# Voeding.net
KiCad netlist of a schematic drawn in Altium Designer
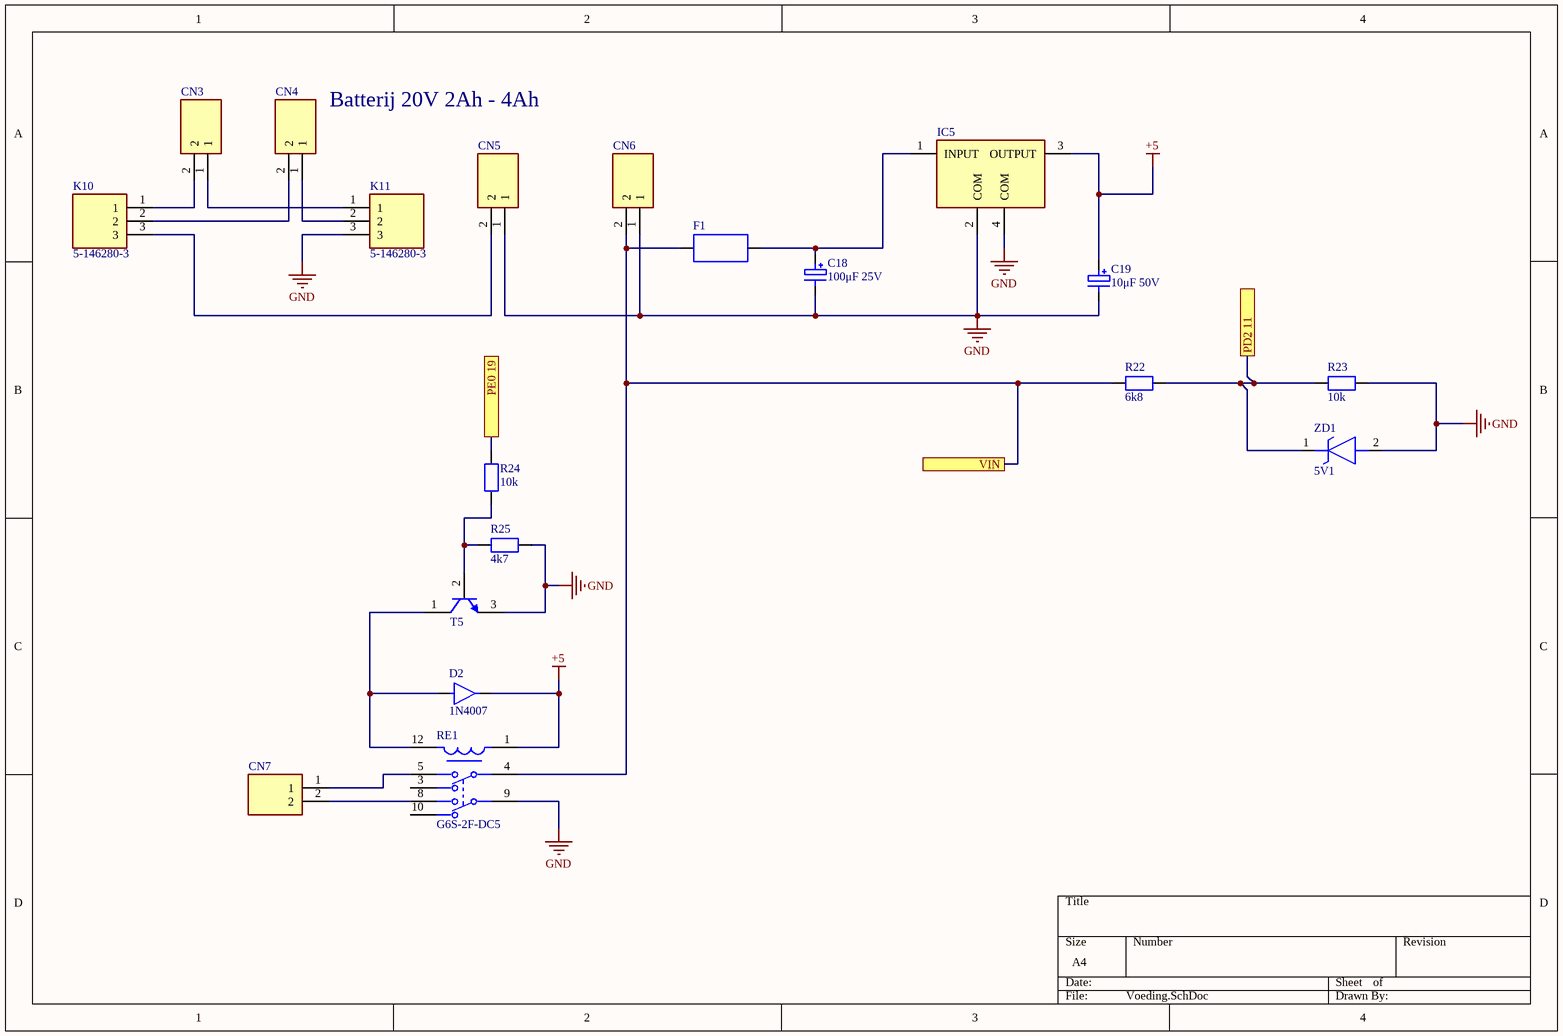
[diagram p0: Voeding.SchDoc]

(export (version "E")
  (design (tool "Eeschema 10.0.6"))
  (components
    (comp (ref "C18")
      (value "100μF 25V")
      (footprint "Elco 100uF 25V")
      (fields
        (field (name "PART NUMBER") "02015A270JAT2A")
        (field (name "MANUFACTURER") "AVX Interconnect / Elco")
      )
      (libsource (lib "Soldeerstation") (part "Condensator Elco"))
    )
    (comp (ref "C19")
      (value "10μF 50V")
      (footprint "Elco 100uF 25V")
      (fields
        (field (name "PART NUMBER") "02015A270JAT2A")
        (field (name "MANUFACTURER") "AVX Interconnect / Elco")
      )
      (libsource (lib "Soldeerstation") (part "Condensator Elco"))
    )
    (comp (ref "CN3")
      (value "282836-2")
      (footprint "Schroefconnector 2 Pin")
      (description "Connector")
      (libsource (lib "Soldeerstation") (part "Schroefconnector 2 Pin L"))
    )
    (comp (ref "CN4")
      (value "282836-2")
      (footprint "Schroefconnector 2 Pin")
      (description "Connector")
      (libsource (lib "Soldeerstation") (part "Schroefconnector 2 Pin L"))
    )
    (comp (ref "CN5")
      (value "282836-2")
      (footprint "Schroefconnector 2 Pin")
      (description "Connector")
      (libsource (lib "Soldeerstation") (part "Schroefconnector 2 Pin L"))
    )
    (comp (ref "CN6")
      (value "282836-2")
      (footprint "Schroefconnector 2 Pin")
      (description "Connector")
      (libsource (lib "Soldeerstation") (part "Schroefconnector 2 Pin L"))
    )
    (comp (ref "CN7")
      (value "282836-2")
      (footprint "Schroefconnector 2 Pin")
      (description "Connector")
      (libsource (lib "") (part "Schroefconnector 2 Pin L_1"))
    )
    (comp (ref "D2")
      (value "1N4007")
      (footprint "1N4007")
      (description "1000 V, 1 A")
      (fields (field (name "VOLTAGE") "100V"))
      (libsource (lib "Soldeerstation") (part "1N4007"))
    )
    (comp (ref "F1")
      (value "696101000002")
      (footprint "FuseHolder")
      (libsource (lib "Soldeerstation") (part "FuseHolder"))
    )
    (comp (ref "IC5")
      (value "TL780-05CKTTR")
      (footprint "DC-DC Convertor")
      (description "IC REG LIN 5V 1.5A DDPAK/TO263-3")
      (libsource (lib "Soldeerstation") (part "DC/DC Convertor"))
    )
    (comp (ref "K10")
      (value "5-146280-3")
      (footprint "3 Pin Header")
      (description "Connector 5-146280-3")
      (fields (field (name "MOUSER2 PART NUMBER") "571-5-146280-3"))
      (libsource (lib "") (part "3 Pin Header_1"))
    )
    (comp (ref "K11")
      (value "5-146280-3")
      (footprint "3 Pin Header")
      (description "Connector 5-146280-3")
      (fields (field (name "MOUSER2 PART NUMBER") "571-5-146280-3"))
      (libsource (lib "Soldeerstation") (part "3 Pin Header"))
    )
    (comp (ref "R22")
      (value "6k8")
      (footprint "Resistor")
      (description "Resistor")
      (fields (field (name "MANUFACTURER") "Vishay Dale") (field (name "PART NUMBER") "CRCW08050000Z0EA"))
      (libsource (lib "Soldeerstation") (part "Resistor"))
    )
    (comp (ref "R23")
      (value "10k")
      (footprint "Resistor")
      (description "Resistor")
      (fields (field (name "MANUFACTURER") "Vishay Dale") (field (name "PART NUMBER") "CRCW08050000Z0EA"))
      (libsource (lib "Soldeerstation") (part "Resistor"))
    )
    (comp (ref "R24")
      (value "10k")
      (footprint "Resistor")
      (description "Resistor")
      (fields (field (name "MANUFACTURER") "Vishay Dale") (field (name "PART NUMBER") "CRCW08050000Z0EA"))
      (libsource (lib "Soldeerstation") (part "Resistor"))
    )
    (comp (ref "R25")
      (value "4k7")
      (footprint "Resistor")
      (description "Resistor")
      (fields (field (name "MANUFACTURER") "Vishay Dale") (field (name "PART NUMBER") "CRCW08050000Z0EA"))
      (libsource (lib "Soldeerstation") (part "Resistor"))
    )
    (comp (ref "RE1")
      (value "G6S-2F-DC5")
      (footprint "Relay")
      (description "RELAY TELECOM DPDT 2A 5VDC")
      (fields
        (field (name "MANUFACTURER") "Omron")
        (field (name "OCTOPART") "https://octopart.com/g6s-2f-dc5-omron-85236")
      )
      (libsource (lib "Soldeerstation") (part "Relay"))
    )
    (comp (ref "T5")
      (value "BC547CZL1G")
      (footprint "BC547C")
      (description "BC547C, 45 V, 100 mA, 500 mW,\r\nhfe = 400")
      (fields (field (name "MANUFACTURER") "On Semiconductor"))
      (libsource (lib "Soldeerstation") (part "BC547C"))
    )
    (comp (ref "ZD1")
      (value "5V1")
      (footprint "ZenerDiode")
      (description "zenerdiode 5,1 V, 500 mW")
      (libsource (lib "Soldeerstation") (part "ZenerDiode"))
    )
  )
  (nets
    (net (code "1") (name "+5") (class "Default")
      (node (ref "C19") (pin "1") (pinfunction "1_1") (pintype "passive"))
      (node (ref "D2") (pin "1") (pinfunction "C_1") (pintype "passive"))
      (node (ref "IC5") (pin "3") (pinfunction "OUTPUT_3") (pintype "power_in"))
      (node (ref "RE1") (pin "1") (pinfunction "1_1") (pintype "passive"))
    )
    (net (code "2") (name "/PD2 11") (class "Default")
      (node (ref "R22") (pin "2") (pinfunction "2_2") (pintype "passive"))
      (node (ref "R23") (pin "1") (pintype "passive"))
      (node (ref "ZD1") (pin "1") (pinfunction "K_1") (pintype "passive"))
    )
    (net (code "3") (name "/PE0 19") (class "Default")
      (node (ref "R24") (pin "2") (pinfunction "2_2") (pintype "passive"))
    )
    (net (code "4") (name "/VIN") (class "Default")
      (node (ref "CN6") (pin "2") (pinfunction "2_2") (pintype "passive"))
      (node (ref "F1") (pin "1") (pinfunction "1_1") (pintype "passive"))
      (node (ref "R22") (pin "1") (pintype "passive"))
      (node (ref "RE1") (pin "4") (pinfunction "4_4") (pintype "passive"))
    )
    (net (code "5") (name "GND") (class "Default")
      (node (ref "C18") (pin "2") (pinfunction "2_2") (pintype "passive"))
      (node (ref "C19") (pin "2") (pinfunction "2_2") (pintype "passive"))
      (node (ref "CN5") (pin "1") (pinfunction "1_1") (pintype "passive"))
      (node (ref "CN6") (pin "1") (pinfunction "1_1") (pintype "passive"))
      (node (ref "IC5") (pin "2") (pinfunction "COM_2") (pintype "passive"))
      (node (ref "IC5") (pin "4") (pinfunction "COM_4") (pintype "passive"))
      (node (ref "K11") (pin "3") (pinfunction "3_3") (pintype "passive"))
      (node (ref "R23") (pin "2") (pinfunction "2_2") (pintype "passive"))
      (node (ref "R25") (pin "2") (pinfunction "2_2") (pintype "passive"))
      (node (ref "RE1") (pin "9") (pinfunction "9_9") (pintype "passive"))
      (node (ref "T5") (pin "3") (pinfunction "E_3") (pintype "passive"))
      (node (ref "ZD1") (pin "2") (pinfunction "A_2") (pintype "passive"))
    )
    (net (code "6") (name "Net-(CN3-Pad1)") (class "Default")
      (node (ref "CN3") (pin "1") (pinfunction "1_1") (pintype "passive"))
      (node (ref "K11") (pin "1") (pinfunction "1_1") (pintype "passive"))
    )
    (net (code "7") (name "Net-(CN3-Pad2)") (class "Default")
      (node (ref "CN3") (pin "2") (pinfunction "2_2") (pintype "passive"))
      (node (ref "K10") (pin "1") (pinfunction "1_1") (pintype "passive"))
    )
    (net (code "8") (name "Net-(CN4-Pad1)") (class "Default")
      (node (ref "CN4") (pin "1") (pinfunction "1_1") (pintype "passive"))
      (node (ref "K11") (pin "2") (pinfunction "2_2") (pintype "passive"))
    )
    (net (code "9") (name "Net-(CN4-Pad2)") (class "Default")
      (node (ref "CN4") (pin "2") (pinfunction "2_2") (pintype "passive"))
      (node (ref "K10") (pin "2") (pinfunction "2_2") (pintype "passive"))
    )
    (net (code "10") (name "Net-(CN5-Pad2)") (class "Default")
      (node (ref "CN5") (pin "2") (pinfunction "2_2") (pintype "passive"))
      (node (ref "K10") (pin "3") (pinfunction "3_3") (pintype "passive"))
    )
    (net (code "11") (name "Net-(CN7-Pad1)") (class "Default")
      (node (ref "CN7") (pin "1") (pinfunction "1_1") (pintype "passive"))
      (node (ref "RE1") (pin "5") (pinfunction "5_5") (pintype "passive"))
    )
    (net (code "12") (name "Net-(CN7-Pad2)") (class "Default")
      (node (ref "CN7") (pin "2") (pinfunction "2_2") (pintype "passive"))
      (node (ref "RE1") (pin "8") (pinfunction "8_8") (pintype "passive"))
    )
    (net (code "13") (name "Net-(D2-A)") (class "Default")
      (node (ref "D2") (pin "2") (pinfunction "A_2") (pintype "passive"))
      (node (ref "RE1") (pin "12") (pinfunction "12_12") (pintype "passive"))
      (node (ref "T5") (pin "1") (pinfunction "C_1") (pintype "passive"))
    )
    (net (code "14") (name "Net-(IC5-INPUT)") (class "Default")
      (node (ref "C18") (pin "1") (pinfunction "1_1") (pintype "passive"))
      (node (ref "F1") (pin "2") (pinfunction "2_2") (pintype "passive"))
      (node (ref "IC5") (pin "1") (pinfunction "INPUT_1") (pintype "power_in"))
    )
    (net (code "15") (name "Net-(T5-B)") (class "Default")
      (node (ref "R24") (pin "1") (pintype "passive"))
      (node (ref "R25") (pin "1") (pintype "passive"))
      (node (ref "T5") (pin "2") (pinfunction "B_2") (pintype "passive"))
    )
    (net (code "16") (name "unconnected-(RE1-Pad3)") (class "Default")
      (node (ref "RE1") (pin "3") (pinfunction "3_3") (pintype "passive"))
    )
    (net (code "17") (name "unconnected-(RE1-Pad10)") (class "Default")
      (node (ref "RE1") (pin "10") (pinfunction "10_10") (pintype "passive"))
    )
  )
)
